# scheme.net
KiCad netlist of a schematic drawn in Altium Designer
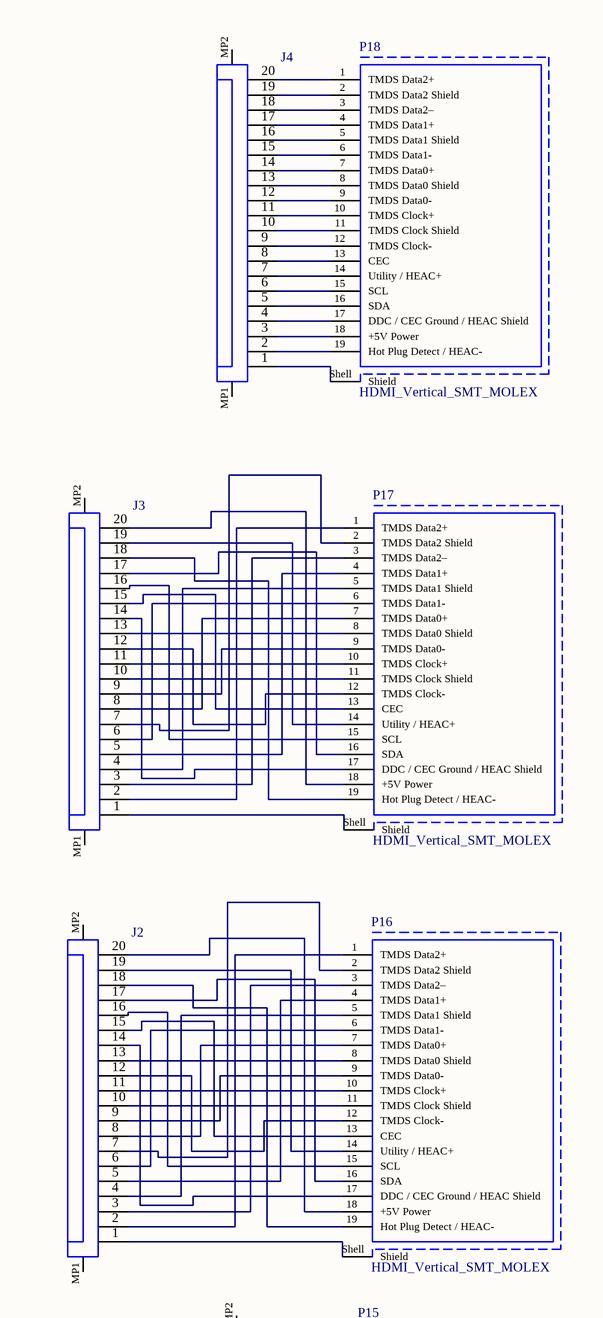
[diagram p0: scheme.SchDoc, top]
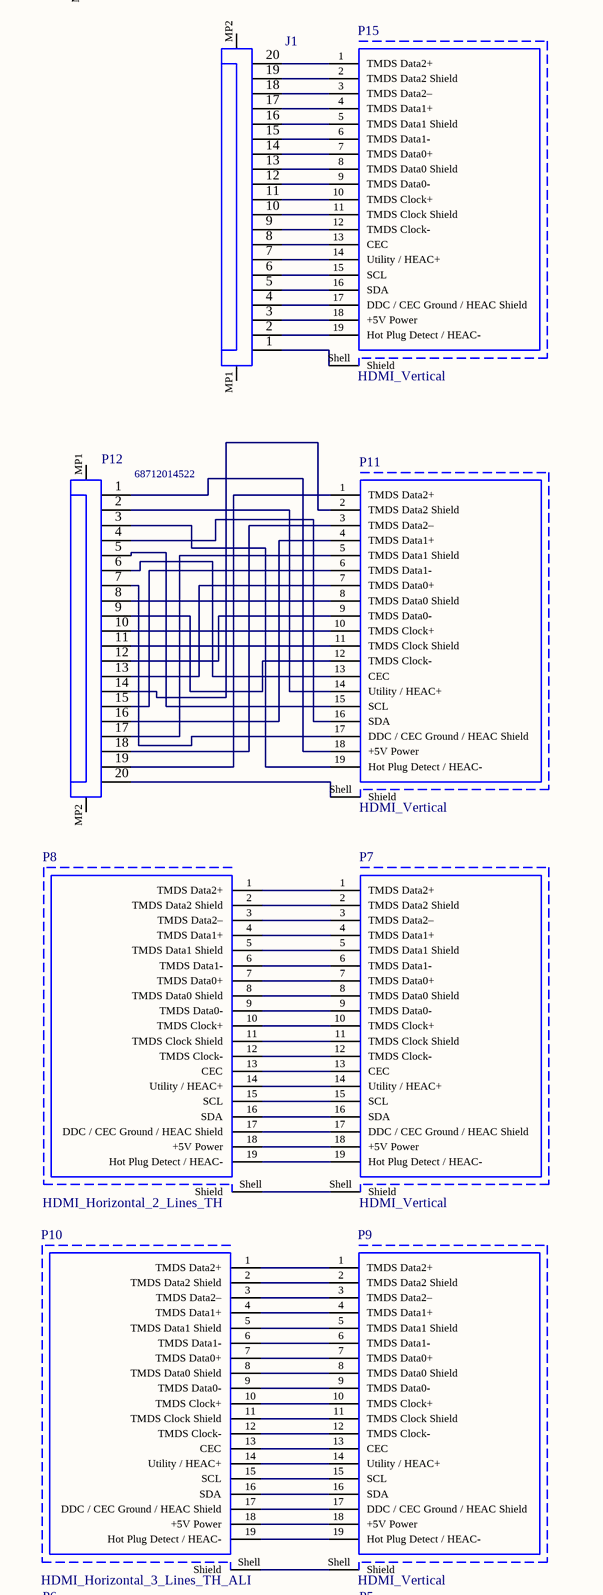
[diagram p1: scheme.SchDoc, centre]
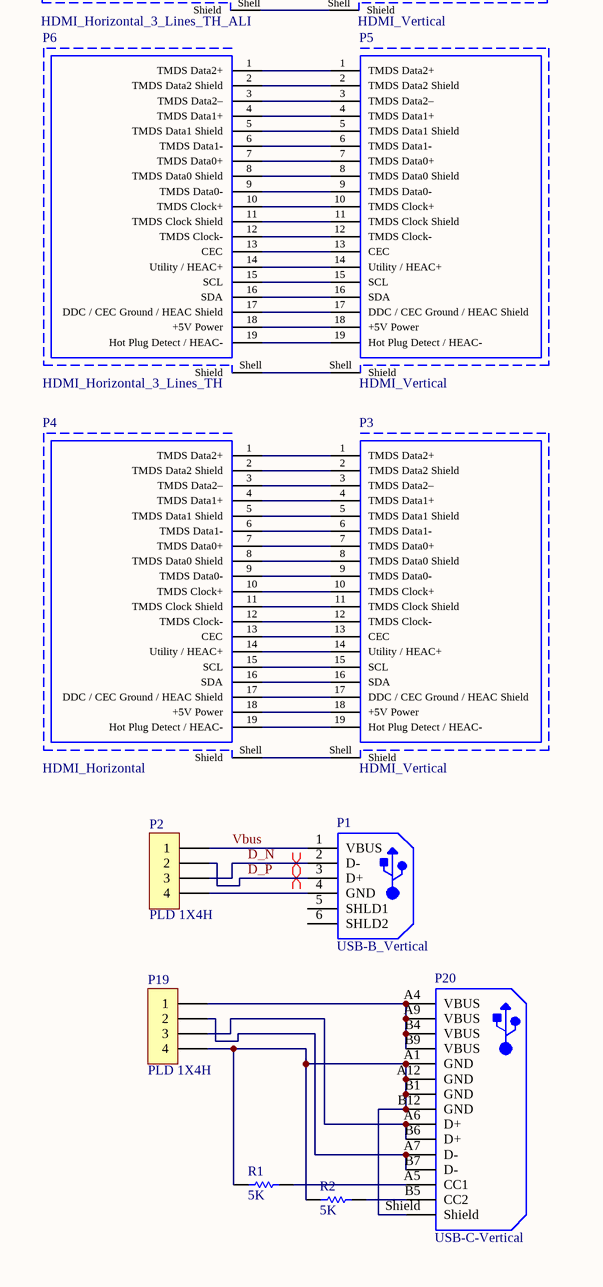
[diagram p2: scheme.SchDoc, bottom]

(export (version "E")
  (design (tool "Eeschema 10.0.6"))
  (components
    (comp (ref "J1")
      (value "68712014522")
      (footprint "FFC_20pin_0.5mm")
      (description "SMT ZIF Connectors WR-FPC, Horizontal, Bottom Contact, pitch 0.5 mm, 20 pins")
      (fields (field (name "MANUFACTURER") "Wurth Elektronik") (field (name "PUBLISHER") "WurthElektronik"))
      (libsource (lib "library") (part "FFC 20 pin"))
    )
    (comp (ref "J2")
      (value "68712014522")
      (footprint "FFC_20pin_0.5mm")
      (description "SMT ZIF Connectors WR-FPC, Horizontal, Bottom Contact, pitch 0.5 mm, 20 pins")
      (fields (field (name "MANUFACTURER") "Wurth Elektronik") (field (name "PUBLISHER") "WurthElektronik"))
      (libsource (lib "library") (part "FFC 20 pin"))
    )
    (comp (ref "J3")
      (value "68712014522")
      (footprint "FFC_20pin_0.5mm")
      (description "SMT ZIF Connectors WR-FPC, Horizontal, Bottom Contact, pitch 0.5 mm, 20 pins")
      (fields (field (name "MANUFACTURER") "Wurth Elektronik") (field (name "PUBLISHER") "WurthElektronik"))
      (libsource (lib "library") (part "FFC 20 pin"))
    )
    (comp (ref "J4")
      (value "68712014522")
      (footprint "FFC_20pin_0.5mm")
      (description "SMT ZIF Connectors WR-FPC, Horizontal, Bottom Contact, pitch 0.5 mm, 20 pins")
      (fields (field (name "MANUFACTURER") "Wurth Elektronik") (field (name "PUBLISHER") "WurthElektronik"))
      (libsource (lib "library") (part "FFC 20 pin"))
    )
    (comp (ref "P1")
      (value "USB-B_Vertical")
      (footprint "USB-B_Vertical")
      (libsource (lib "library") (part "USB-B_Vertical"))
    )
    (comp (ref "P2")
      (value "PLD 1X4H")
      (footprint "PLD 1X4H")
      (description "Header, 4-Pin, SIngle row, Right Angle")
      (libsource (lib "library") (part "PLD 1X4H"))
    )
    (comp (ref "P3")
      (value "HDMI_Vertical")
      (footprint "HDMI Vertical")
      (libsource (lib "library") (part "HDMI_Vertical"))
    )
    (comp (ref "P4")
      (value "HDMI_Horizontal")
      (footprint "HDMI HORIZONTAL")
      (libsource (lib "library") (part "HDMI_Horizontal"))
    )
    (comp (ref "P5")
      (value "HDMI_Vertical")
      (footprint "HDMI Vertical")
      (libsource (lib "library") (part "HDMI_Vertical"))
    )
    (comp (ref "P6")
      (value "HDMI_Horizontal_3_Lines_TH")
      (footprint "HDMI HORIZONTAL 3 LINES TH")
      (libsource (lib "library") (part "HDMI_Horizontal_3_Lines_TH"))
    )
    (comp (ref "P7")
      (value "HDMI_Vertical")
      (footprint "HDMI Vertical")
      (libsource (lib "library") (part "HDMI_Vertical"))
    )
    (comp (ref "P8")
      (value "HDMI_Horizontal_2_Lines_TH")
      (footprint "HDMI HORIZONTAL 2 LINES TH")
      (libsource (lib "library") (part "HDMI_Horizontal_2_Lines_TH"))
    )
    (comp (ref "P9")
      (value "HDMI_Vertical")
      (footprint "HDMI Vertical")
      (libsource (lib "library") (part "HDMI_Vertical"))
    )
    (comp (ref "P10")
      (value "HDMI_Horizontal_3_Lines_TH_ALI")
      (footprint "HDMI HORIZONTAL 3 LINES TH ALI")
      (libsource (lib "library") (part "HDMI_Horizontal_3_Lines_TH_ALI"))
    )
    (comp (ref "P11")
      (value "HDMI_Vertical")
      (footprint "HDMI Vertical")
      (libsource (lib "library") (part "HDMI_Vertical"))
    )
    (comp (ref "P12")
      (value "68712014522")
      (footprint "68712014522")
      (description "SMT ZIF Connectors WR-FPC, Horizontal, Bottom Contact, pitch 0.5 mm, 20 pins")
      (fields (field (name "MANUFACTURER") "Wurth Elektronik") (field (name "PUBLISHER") "WurthElektronik"))
      (libsource (lib "library") (part "CMP-1502-01535-1"))
    )
    (comp (ref "P15")
      (value "HDMI_Vertical")
      (footprint "HDMI Vertical")
      (libsource (lib "library") (part "HDMI_Vertical"))
    )
    (comp (ref "P16")
      (value "HDMI_Vertical_SMT_MOLEX")
      (footprint "HDMI VERTICAL SMT")
      (libsource (lib "library") (part "HDMI_Vertical_SMT_MOLEX"))
    )
    (comp (ref "P17")
      (value "HDMI_Vertical_SMT_MOLEX")
      (footprint "HDMI VERTICAL SMT")
      (libsource (lib "library") (part "HDMI_Vertical_SMT_MOLEX"))
    )
    (comp (ref "P18")
      (value "HDMI_Vertical_SMT_MOLEX")
      (footprint "HDMI VERTICAL SMT")
      (libsource (lib "library") (part "HDMI_Vertical_SMT_MOLEX"))
    )
    (comp (ref "P19")
      (value "PLD 1X4H")
      (footprint "PLD 1X4H")
      (description "Header, 4-Pin, SIngle row, Right Angle")
      (libsource (lib "library") (part "PLD 1X4H"))
    )
    (comp (ref "P20")
      (value "USB-C-Vertical")
      (footprint "USB-C")
      (libsource (lib "library") (part "USB-C-Vertical"))
    )
    (comp (ref "R1")
      (value "5K")
      (footprint "1206")
      (description "Resistor 1206")
      (libsource (lib "library") (part "Resistor"))
    )
    (comp (ref "R2")
      (value "5K")
      (footprint "1206")
      (description "Resistor 1206")
      (libsource (lib "library") (part "Resistor"))
    )
  )
  (nets
    (net (code "1") (name "/D_N") (class "Default")
      (node (ref "P1") (pin "2") (pinfunction "D-_2") (pintype "passive"))
      (node (ref "P2") (pin "3") (pinfunction "3_3") (pintype "passive"))
    )
    (net (code "2") (name "/D_P") (class "Default")
      (node (ref "P1") (pin "3") (pinfunction "D+_3") (pintype "passive"))
      (node (ref "P2") (pin "2") (pinfunction "2_2") (pintype "passive"))
    )
    (net (code "3") (name "/Vbus") (class "Default")
      (node (ref "P1") (pin "1") (pinfunction "VBUS_1") (pintype "passive"))
      (node (ref "P2") (pin "1") (pinfunction "1_1") (pintype "passive"))
    )
    (net (code "4") (name "Net-(P1-GND)") (class "Default")
      (node (ref "P1") (pin "4") (pinfunction "GND_4") (pintype "passive"))
      (node (ref "P2") (pin "4") (pinfunction "4_4") (pintype "passive"))
    )
    (net (code "5") (name "Net-(P3-+5V_Power)") (class "Default")
      (node (ref "P3") (pin "18") (pinfunction "+5V_Power_18") (pintype "passive"))
      (node (ref "P4") (pin "18") (pinfunction "+5V_Power_18") (pintype "passive"))
    )
    (net (code "6") (name "Net-(P3-CEC)") (class "Default")
      (node (ref "P3") (pin "13") (pinfunction "CEC_13") (pintype "passive"))
      (node (ref "P4") (pin "13") (pinfunction "CEC_13") (pintype "passive"))
    )
    (net (code "7") (name "Net-(P3-DDC_{slash}_CEC_Ground_{slash}_HEAC_Shield)") (class "Default")
      (node (ref "P3") (pin "17") (pinfunction "DDC_/_CEC_Ground_/_HEAC_Shield_17") (pintype "passive"))
      (node (ref "P4") (pin "17") (pinfunction "DDC_/_CEC_Ground_/_HEAC_Shield_17") (pintype "passive"))
    )
    (net (code "8") (name "Net-(P3-Hot_Plug_Detect_{slash}_HEAC-)") (class "Default")
      (node (ref "P3") (pin "19") (pinfunction "Hot_Plug_Detect_/_HEAC-_19") (pintype "passive"))
      (node (ref "P4") (pin "19") (pinfunction "Hot_Plug_Detect_/_HEAC-_19") (pintype "passive"))
    )
    (net (code "9") (name "Net-(P3-SCL)") (class "Default")
      (node (ref "P3") (pin "15") (pinfunction "SCL_15") (pintype "passive"))
      (node (ref "P4") (pin "15") (pinfunction "SCL_15") (pintype "passive"))
    )
    (net (code "10") (name "Net-(P3-SDA)") (class "Default")
      (node (ref "P3") (pin "16") (pinfunction "SDA_16") (pintype "passive"))
      (node (ref "P4") (pin "16") (pinfunction "SDA_16") (pintype "passive"))
    )
    (net (code "11") (name "Net-(P3-Shield)") (class "Default")
      (node (ref "P3") (pin "Shell") (pinfunction "Shield_Shell") (pintype "passive"))
      (node (ref "P4") (pin "Shell") (pinfunction "Shield_Shell") (pintype "passive"))
    )
    (net (code "12") (name "Net-(P3-TMDS_Clock+)") (class "Default")
      (node (ref "P3") (pin "10") (pinfunction "TMDS_Clock+_10") (pintype "passive"))
      (node (ref "P4") (pin "10") (pinfunction "TMDS_Clock+_10") (pintype "passive"))
    )
    (net (code "13") (name "Net-(P3-TMDS_Clock-)") (class "Default")
      (node (ref "P3") (pin "12") (pinfunction "TMDS_Clock-_12") (pintype "passive"))
      (node (ref "P4") (pin "12") (pinfunction "TMDS_Clock-_12") (pintype "passive"))
    )
    (net (code "14") (name "Net-(P3-TMDS_Clock_Shield)") (class "Default")
      (node (ref "P3") (pin "11") (pinfunction "TMDS_Clock_Shield_11") (pintype "passive"))
      (node (ref "P4") (pin "11") (pinfunction "TMDS_Clock_Shield_11") (pintype "passive"))
    )
    (net (code "15") (name "Net-(P3-TMDS_Data0+)") (class "Default")
      (node (ref "P3") (pin "7") (pinfunction "TMDS_Data0+_7") (pintype "passive"))
      (node (ref "P4") (pin "7") (pinfunction "TMDS_Data0+_7") (pintype "passive"))
    )
    (net (code "16") (name "Net-(P3-TMDS_Data0-)") (class "Default")
      (node (ref "P3") (pin "9") (pinfunction "TMDS_Data0-_9") (pintype "passive"))
      (node (ref "P4") (pin "9") (pinfunction "TMDS_Data0-_9") (pintype "passive"))
    )
    (net (code "17") (name "Net-(P3-TMDS_Data0_Shield)") (class "Default")
      (node (ref "P3") (pin "8") (pinfunction "TMDS_Data0_Shield_8") (pintype "passive"))
      (node (ref "P4") (pin "8") (pinfunction "TMDS_Data0_Shield_8") (pintype "passive"))
    )
    (net (code "18") (name "Net-(P3-TMDS_Data1+)") (class "Default")
      (node (ref "P3") (pin "4") (pinfunction "TMDS_Data1+_4") (pintype "passive"))
      (node (ref "P4") (pin "4") (pinfunction "TMDS_Data1+_4") (pintype "passive"))
    )
    (net (code "19") (name "Net-(P3-TMDS_Data1-)") (class "Default")
      (node (ref "P3") (pin "6") (pinfunction "TMDS_Data1-_6") (pintype "passive"))
      (node (ref "P4") (pin "6") (pinfunction "TMDS_Data1-_6") (pintype "passive"))
    )
    (net (code "20") (name "Net-(P3-TMDS_Data1_Shield)") (class "Default")
      (node (ref "P3") (pin "5") (pinfunction "TMDS_Data1_Shield_5") (pintype "passive"))
      (node (ref "P4") (pin "5") (pinfunction "TMDS_Data1_Shield_5") (pintype "passive"))
    )
    (net (code "21") (name "Net-(P3-TMDS_Data2+)") (class "Default")
      (node (ref "P3") (pin "1") (pinfunction "TMDS_Data2+_1") (pintype "passive"))
      (node (ref "P4") (pin "1") (pinfunction "TMDS_Data2+_1") (pintype "passive"))
    )
    (net (code "22") (name "Net-(P3-TMDS_Data2_Shield)") (class "Default")
      (node (ref "P3") (pin "2") (pinfunction "TMDS_Data2_Shield_2") (pintype "passive"))
      (node (ref "P4") (pin "2") (pinfunction "TMDS_Data2_Shield_2") (pintype "passive"))
    )
    (net (code "23") (name "Net-(P3-TMDS_Data2–)") (class "Default")
      (node (ref "P3") (pin "3") (pinfunction "TMDS_Data2–_3") (pintype "passive"))
      (node (ref "P4") (pin "3") (pinfunction "TMDS_Data2–_3") (pintype "passive"))
    )
    (net (code "24") (name "Net-(P3-Utility_{slash}_HEAC+)") (class "Default")
      (node (ref "P3") (pin "14") (pinfunction "Utility_/_HEAC+_14") (pintype "passive"))
      (node (ref "P4") (pin "14") (pinfunction "Utility_/_HEAC+_14") (pintype "passive"))
    )
    (net (code "25") (name "Net-(P5-+5V_Power)") (class "Default")
      (node (ref "P5") (pin "18") (pinfunction "+5V_Power_18") (pintype "passive"))
      (node (ref "P6") (pin "18") (pinfunction "+5V_Power_18") (pintype "passive"))
    )
    (net (code "26") (name "Net-(P5-CEC)") (class "Default")
      (node (ref "P5") (pin "13") (pinfunction "CEC_13") (pintype "passive"))
      (node (ref "P6") (pin "13") (pinfunction "CEC_13") (pintype "passive"))
    )
    (net (code "27") (name "Net-(P5-DDC_{slash}_CEC_Ground_{slash}_HEAC_Shield)") (class "Default")
      (node (ref "P5") (pin "17") (pinfunction "DDC_/_CEC_Ground_/_HEAC_Shield_17") (pintype "passive"))
      (node (ref "P6") (pin "17") (pinfunction "DDC_/_CEC_Ground_/_HEAC_Shield_17") (pintype "passive"))
    )
    (net (code "28") (name "Net-(P5-Hot_Plug_Detect_{slash}_HEAC-)") (class "Default")
      (node (ref "P5") (pin "19") (pinfunction "Hot_Plug_Detect_/_HEAC-_19") (pintype "passive"))
      (node (ref "P6") (pin "19") (pinfunction "Hot_Plug_Detect_/_HEAC-_19") (pintype "passive"))
    )
    (net (code "29") (name "Net-(P5-SCL)") (class "Default")
      (node (ref "P5") (pin "15") (pinfunction "SCL_15") (pintype "passive"))
      (node (ref "P6") (pin "15") (pinfunction "SCL_15") (pintype "passive"))
    )
    (net (code "30") (name "Net-(P5-SDA)") (class "Default")
      (node (ref "P5") (pin "16") (pinfunction "SDA_16") (pintype "passive"))
      (node (ref "P6") (pin "16") (pinfunction "SDA_16") (pintype "passive"))
    )
    (net (code "31") (name "Net-(P5-Shield)") (class "Default")
      (node (ref "P5") (pin "Shell") (pinfunction "Shield_Shell") (pintype "passive"))
      (node (ref "P6") (pin "Shell") (pinfunction "Shield_Shell") (pintype "passive"))
    )
    (net (code "32") (name "Net-(P5-TMDS_Clock+)") (class "Default")
      (node (ref "P5") (pin "10") (pinfunction "TMDS_Clock+_10") (pintype "passive"))
      (node (ref "P6") (pin "10") (pinfunction "TMDS_Clock+_10") (pintype "passive"))
    )
    (net (code "33") (name "Net-(P5-TMDS_Clock-)") (class "Default")
      (node (ref "P5") (pin "12") (pinfunction "TMDS_Clock-_12") (pintype "passive"))
      (node (ref "P6") (pin "12") (pinfunction "TMDS_Clock-_12") (pintype "passive"))
    )
    (net (code "34") (name "Net-(P5-TMDS_Clock_Shield)") (class "Default")
      (node (ref "P5") (pin "11") (pinfunction "TMDS_Clock_Shield_11") (pintype "passive"))
      (node (ref "P6") (pin "11") (pinfunction "TMDS_Clock_Shield_11") (pintype "passive"))
    )
    (net (code "35") (name "Net-(P5-TMDS_Data0+)") (class "Default")
      (node (ref "P5") (pin "7") (pinfunction "TMDS_Data0+_7") (pintype "passive"))
      (node (ref "P6") (pin "7") (pinfunction "TMDS_Data0+_7") (pintype "passive"))
    )
    (net (code "36") (name "Net-(P5-TMDS_Data0-)") (class "Default")
      (node (ref "P5") (pin "9") (pinfunction "TMDS_Data0-_9") (pintype "passive"))
      (node (ref "P6") (pin "9") (pinfunction "TMDS_Data0-_9") (pintype "passive"))
    )
    (net (code "37") (name "Net-(P5-TMDS_Data0_Shield)") (class "Default")
      (node (ref "P5") (pin "8") (pinfunction "TMDS_Data0_Shield_8") (pintype "passive"))
      (node (ref "P6") (pin "8") (pinfunction "TMDS_Data0_Shield_8") (pintype "passive"))
    )
    (net (code "38") (name "Net-(P5-TMDS_Data1+)") (class "Default")
      (node (ref "P5") (pin "4") (pinfunction "TMDS_Data1+_4") (pintype "passive"))
      (node (ref "P6") (pin "4") (pinfunction "TMDS_Data1+_4") (pintype "passive"))
    )
    (net (code "39") (name "Net-(P5-TMDS_Data1-)") (class "Default")
      (node (ref "P5") (pin "6") (pinfunction "TMDS_Data1-_6") (pintype "passive"))
      (node (ref "P6") (pin "6") (pinfunction "TMDS_Data1-_6") (pintype "passive"))
    )
    (net (code "40") (name "Net-(P5-TMDS_Data1_Shield)") (class "Default")
      (node (ref "P5") (pin "5") (pinfunction "TMDS_Data1_Shield_5") (pintype "passive"))
      (node (ref "P6") (pin "5") (pinfunction "TMDS_Data1_Shield_5") (pintype "passive"))
    )
    (net (code "41") (name "Net-(P5-TMDS_Data2+)") (class "Default")
      (node (ref "P5") (pin "1") (pinfunction "TMDS_Data2+_1") (pintype "passive"))
      (node (ref "P6") (pin "1") (pinfunction "TMDS_Data2+_1") (pintype "passive"))
    )
    (net (code "42") (name "Net-(P5-TMDS_Data2_Shield)") (class "Default")
      (node (ref "P5") (pin "2") (pinfunction "TMDS_Data2_Shield_2") (pintype "passive"))
      (node (ref "P6") (pin "2") (pinfunction "TMDS_Data2_Shield_2") (pintype "passive"))
    )
    (net (code "43") (name "Net-(P5-TMDS_Data2–)") (class "Default")
      (node (ref "P5") (pin "3") (pinfunction "TMDS_Data2–_3") (pintype "passive"))
      (node (ref "P6") (pin "3") (pinfunction "TMDS_Data2–_3") (pintype "passive"))
    )
    (net (code "44") (name "Net-(P5-Utility_{slash}_HEAC+)") (class "Default")
      (node (ref "P5") (pin "14") (pinfunction "Utility_/_HEAC+_14") (pintype "passive"))
      (node (ref "P6") (pin "14") (pinfunction "Utility_/_HEAC+_14") (pintype "passive"))
    )
    (net (code "45") (name "Net-(P7-+5V_Power)") (class "Default")
      (node (ref "P7") (pin "18") (pinfunction "+5V_Power_18") (pintype "passive"))
      (node (ref "P8") (pin "18") (pinfunction "+5V_Power_18") (pintype "passive"))
    )
    (net (code "46") (name "Net-(P7-CEC)") (class "Default")
      (node (ref "P7") (pin "13") (pinfunction "CEC_13") (pintype "passive"))
      (node (ref "P8") (pin "13") (pinfunction "CEC_13") (pintype "passive"))
    )
    (net (code "47") (name "Net-(P7-DDC_{slash}_CEC_Ground_{slash}_HEAC_Shield)") (class "Default")
      (node (ref "P7") (pin "17") (pinfunction "DDC_/_CEC_Ground_/_HEAC_Shield_17") (pintype "passive"))
      (node (ref "P8") (pin "17") (pinfunction "DDC_/_CEC_Ground_/_HEAC_Shield_17") (pintype "passive"))
    )
    (net (code "48") (name "Net-(P7-Hot_Plug_Detect_{slash}_HEAC-)") (class "Default")
      (node (ref "P7") (pin "19") (pinfunction "Hot_Plug_Detect_/_HEAC-_19") (pintype "passive"))
      (node (ref "P8") (pin "19") (pinfunction "Hot_Plug_Detect_/_HEAC-_19") (pintype "passive"))
    )
    (net (code "49") (name "Net-(P7-SCL)") (class "Default")
      (node (ref "P7") (pin "15") (pinfunction "SCL_15") (pintype "passive"))
      (node (ref "P8") (pin "15") (pinfunction "SCL_15") (pintype "passive"))
    )
    (net (code "50") (name "Net-(P7-SDA)") (class "Default")
      (node (ref "P7") (pin "16") (pinfunction "SDA_16") (pintype "passive"))
      (node (ref "P8") (pin "16") (pinfunction "SDA_16") (pintype "passive"))
    )
    (net (code "51") (name "Net-(P7-Shield)") (class "Default")
      (node (ref "P7") (pin "Shell") (pinfunction "Shield_Shell") (pintype "passive"))
      (node (ref "P8") (pin "Shell") (pinfunction "Shield_Shell") (pintype "passive"))
    )
    (net (code "52") (name "Net-(P7-TMDS_Clock+)") (class "Default")
      (node (ref "P7") (pin "10") (pinfunction "TMDS_Clock+_10") (pintype "passive"))
      (node (ref "P8") (pin "10") (pinfunction "TMDS_Clock+_10") (pintype "passive"))
    )
    (net (code "53") (name "Net-(P7-TMDS_Clock-)") (class "Default")
      (node (ref "P7") (pin "12") (pinfunction "TMDS_Clock-_12") (pintype "passive"))
      (node (ref "P8") (pin "12") (pinfunction "TMDS_Clock-_12") (pintype "passive"))
    )
    (net (code "54") (name "Net-(P7-TMDS_Clock_Shield)") (class "Default")
      (node (ref "P7") (pin "11") (pinfunction "TMDS_Clock_Shield_11") (pintype "passive"))
      (node (ref "P8") (pin "11") (pinfunction "TMDS_Clock_Shield_11") (pintype "passive"))
    )
    (net (code "55") (name "Net-(P7-TMDS_Data0+)") (class "Default")
      (node (ref "P7") (pin "7") (pinfunction "TMDS_Data0+_7") (pintype "passive"))
      (node (ref "P8") (pin "7") (pinfunction "TMDS_Data0+_7") (pintype "passive"))
    )
    (net (code "56") (name "Net-(P7-TMDS_Data0-)") (class "Default")
      (node (ref "P7") (pin "9") (pinfunction "TMDS_Data0-_9") (pintype "passive"))
      (node (ref "P8") (pin "9") (pinfunction "TMDS_Data0-_9") (pintype "passive"))
    )
    (net (code "57") (name "Net-(P7-TMDS_Data0_Shield)") (class "Default")
      (node (ref "P7") (pin "8") (pinfunction "TMDS_Data0_Shield_8") (pintype "passive"))
      (node (ref "P8") (pin "8") (pinfunction "TMDS_Data0_Shield_8") (pintype "passive"))
    )
    (net (code "58") (name "Net-(P7-TMDS_Data1+)") (class "Default")
      (node (ref "P7") (pin "4") (pinfunction "TMDS_Data1+_4") (pintype "passive"))
      (node (ref "P8") (pin "4") (pinfunction "TMDS_Data1+_4") (pintype "passive"))
    )
    (net (code "59") (name "Net-(P7-TMDS_Data1-)") (class "Default")
      (node (ref "P7") (pin "6") (pinfunction "TMDS_Data1-_6") (pintype "passive"))
      (node (ref "P8") (pin "6") (pinfunction "TMDS_Data1-_6") (pintype "passive"))
    )
    (net (code "60") (name "Net-(P7-TMDS_Data1_Shield)") (class "Default")
      (node (ref "P7") (pin "5") (pinfunction "TMDS_Data1_Shield_5") (pintype "passive"))
      (node (ref "P8") (pin "5") (pinfunction "TMDS_Data1_Shield_5") (pintype "passive"))
    )
    (net (code "61") (name "Net-(P7-TMDS_Data2+)") (class "Default")
      (node (ref "P7") (pin "1") (pinfunction "TMDS_Data2+_1") (pintype "passive"))
      (node (ref "P8") (pin "1") (pinfunction "TMDS_Data2+_1") (pintype "passive"))
    )
    (net (code "62") (name "Net-(P7-TMDS_Data2_Shield)") (class "Default")
      (node (ref "P7") (pin "2") (pinfunction "TMDS_Data2_Shield_2") (pintype "passive"))
      (node (ref "P8") (pin "2") (pinfunction "TMDS_Data2_Shield_2") (pintype "passive"))
    )
    (net (code "63") (name "Net-(P7-TMDS_Data2–)") (class "Default")
      (node (ref "P7") (pin "3") (pinfunction "TMDS_Data2–_3") (pintype "passive"))
      (node (ref "P8") (pin "3") (pinfunction "TMDS_Data2–_3") (pintype "passive"))
    )
    (net (code "64") (name "Net-(P7-Utility_{slash}_HEAC+)") (class "Default")
      (node (ref "P7") (pin "14") (pinfunction "Utility_/_HEAC+_14") (pintype "passive"))
      (node (ref "P8") (pin "14") (pinfunction "Utility_/_HEAC+_14") (pintype "passive"))
    )
    (net (code "65") (name "Net-(P10-+5V_Power)") (class "Default")
      (node (ref "P10") (pin "18") (pinfunction "+5V_Power_18") (pintype "passive"))
      (node (ref "P9") (pin "18") (pinfunction "+5V_Power_18") (pintype "passive"))
    )
    (net (code "66") (name "Net-(P10-CEC)") (class "Default")
      (node (ref "P10") (pin "13") (pinfunction "CEC_13") (pintype "passive"))
      (node (ref "P9") (pin "13") (pinfunction "CEC_13") (pintype "passive"))
    )
    (net (code "67") (name "Net-(P10-DDC_{slash}_CEC_Ground_{slash}_HEAC_Shield)") (class "Default")
      (node (ref "P10") (pin "17") (pinfunction "DDC_/_CEC_Ground_/_HEAC_Shield_17") (pintype "passive"))
      (node (ref "P9") (pin "17") (pinfunction "DDC_/_CEC_Ground_/_HEAC_Shield_17") (pintype "passive"))
    )
    (net (code "68") (name "Net-(P10-Hot_Plug_Detect_{slash}_HEAC-)") (class "Default")
      (node (ref "P10") (pin "19") (pinfunction "Hot_Plug_Detect_/_HEAC-_19") (pintype "passive"))
      (node (ref "P9") (pin "19") (pinfunction "Hot_Plug_Detect_/_HEAC-_19") (pintype "passive"))
    )
    (net (code "69") (name "Net-(P10-SCL)") (class "Default")
      (node (ref "P10") (pin "15") (pinfunction "SCL_15") (pintype "passive"))
      (node (ref "P9") (pin "15") (pinfunction "SCL_15") (pintype "passive"))
    )
    (net (code "70") (name "Net-(P10-SDA)") (class "Default")
      (node (ref "P10") (pin "16") (pinfunction "SDA_16") (pintype "passive"))
      (node (ref "P9") (pin "16") (pinfunction "SDA_16") (pintype "passive"))
    )
    (net (code "71") (name "Net-(P10-Shield)") (class "Default")
      (node (ref "P10") (pin "Shell") (pinfunction "Shield_Shell") (pintype "passive"))
      (node (ref "P9") (pin "Shell") (pinfunction "Shield_Shell") (pintype "passive"))
    )
    (net (code "72") (name "Net-(P10-TMDS_Clock+)") (class "Default")
      (node (ref "P10") (pin "10") (pinfunction "TMDS_Clock+_10") (pintype "passive"))
      (node (ref "P9") (pin "10") (pinfunction "TMDS_Clock+_10") (pintype "passive"))
    )
    (net (code "73") (name "Net-(P10-TMDS_Clock-)") (class "Default")
      (node (ref "P10") (pin "12") (pinfunction "TMDS_Clock-_12") (pintype "passive"))
      (node (ref "P9") (pin "12") (pinfunction "TMDS_Clock-_12") (pintype "passive"))
    )
    (net (code "74") (name "Net-(P10-TMDS_Clock_Shield)") (class "Default")
      (node (ref "P10") (pin "11") (pinfunction "TMDS_Clock_Shield_11") (pintype "passive"))
      (node (ref "P9") (pin "11") (pinfunction "TMDS_Clock_Shield_11") (pintype "passive"))
    )
    (net (code "75") (name "Net-(P10-TMDS_Data0+)") (class "Default")
      (node (ref "P10") (pin "7") (pinfunction "TMDS_Data0+_7") (pintype "passive"))
      (node (ref "P9") (pin "7") (pinfunction "TMDS_Data0+_7") (pintype "passive"))
    )
    (net (code "76") (name "Net-(P10-TMDS_Data0-)") (class "Default")
      (node (ref "P10") (pin "9") (pinfunction "TMDS_Data0-_9") (pintype "passive"))
      (node (ref "P9") (pin "9") (pinfunction "TMDS_Data0-_9") (pintype "passive"))
    )
    (net (code "77") (name "Net-(P10-TMDS_Data0_Shield)") (class "Default")
      (node (ref "P10") (pin "8") (pinfunction "TMDS_Data0_Shield_8") (pintype "passive"))
      (node (ref "P9") (pin "8") (pinfunction "TMDS_Data0_Shield_8") (pintype "passive"))
    )
    (net (code "78") (name "Net-(P10-TMDS_Data1+)") (class "Default")
      (node (ref "P10") (pin "4") (pinfunction "TMDS_Data1+_4") (pintype "passive"))
      (node (ref "P9") (pin "4") (pinfunction "TMDS_Data1+_4") (pintype "passive"))
    )
    (net (code "79") (name "Net-(P10-TMDS_Data1-)") (class "Default")
      (node (ref "P10") (pin "6") (pinfunction "TMDS_Data1-_6") (pintype "passive"))
      (node (ref "P9") (pin "6") (pinfunction "TMDS_Data1-_6") (pintype "passive"))
    )
    (net (code "80") (name "Net-(P10-TMDS_Data1_Shield)") (class "Default")
      (node (ref "P10") (pin "5") (pinfunction "TMDS_Data1_Shield_5") (pintype "passive"))
      (node (ref "P9") (pin "5") (pinfunction "TMDS_Data1_Shield_5") (pintype "passive"))
    )
    (net (code "81") (name "Net-(P10-TMDS_Data2+)") (class "Default")
      (node (ref "P10") (pin "1") (pinfunction "TMDS_Data2+_1") (pintype "passive"))
      (node (ref "P9") (pin "1") (pinfunction "TMDS_Data2+_1") (pintype "passive"))
    )
    (net (code "82") (name "Net-(P10-TMDS_Data2_Shield)") (class "Default")
      (node (ref "P10") (pin "2") (pinfunction "TMDS_Data2_Shield_2") (pintype "passive"))
      (node (ref "P9") (pin "2") (pinfunction "TMDS_Data2_Shield_2") (pintype "passive"))
    )
    (net (code "83") (name "Net-(P10-TMDS_Data2–)") (class "Default")
      (node (ref "P10") (pin "3") (pinfunction "TMDS_Data2–_3") (pintype "passive"))
      (node (ref "P9") (pin "3") (pinfunction "TMDS_Data2–_3") (pintype "passive"))
    )
    (net (code "84") (name "Net-(P10-Utility_{slash}_HEAC+)") (class "Default")
      (node (ref "P10") (pin "14") (pinfunction "Utility_/_HEAC+_14") (pintype "passive"))
      (node (ref "P9") (pin "14") (pinfunction "Utility_/_HEAC+_14") (pintype "passive"))
    )
    (net (code "85") (name "Net-(P11-+5V_Power)") (class "Default")
      (node (ref "P11") (pin "18") (pinfunction "+5V_Power_18") (pintype "passive"))
      (node (ref "P12") (pin "1") (pinfunction "1_1") (pintype "passive"))
    )
    (net (code "86") (name "Net-(P11-CEC)") (class "Default")
      (node (ref "P11") (pin "13") (pinfunction "CEC_13") (pintype "passive"))
      (node (ref "P12") (pin "6") (pinfunction "6_6") (pintype "passive"))
    )
    (net (code "87") (name "Net-(P11-DDC_{slash}_CEC_Ground_{slash}_HEAC_Shield)") (class "Default")
      (node (ref "P11") (pin "17") (pinfunction "DDC_/_CEC_Ground_/_HEAC_Shield_17") (pintype "passive"))
      (node (ref "P12") (pin "7") (pinfunction "7_7") (pintype "passive"))
    )
    (net (code "88") (name "Net-(P11-Hot_Plug_Detect_{slash}_HEAC-)") (class "Default")
      (node (ref "P11") (pin "19") (pinfunction "Hot_Plug_Detect_/_HEAC-_19") (pintype "passive"))
      (node (ref "P12") (pin "3") (pinfunction "3_3") (pintype "passive"))
    )
    (net (code "89") (name "Net-(P11-SCL)") (class "Default")
      (node (ref "P11") (pin "15") (pinfunction "SCL_15") (pintype "passive"))
      (node (ref "P12") (pin "5") (pinfunction "5_5") (pintype "passive"))
    )
    (net (code "90") (name "Net-(P11-SDA)") (class "Default")
      (node (ref "P11") (pin "16") (pinfunction "SDA_16") (pintype "passive"))
      (node (ref "P12") (pin "4") (pinfunction "4_4") (pintype "passive"))
    )
    (net (code "91") (name "Net-(P11-Shield)") (class "Default")
      (node (ref "P11") (pin "Shell") (pinfunction "Shield_Shell") (pintype "passive"))
      (node (ref "P12") (pin "20") (pinfunction "20_20") (pintype "passive"))
    )
    (net (code "92") (name "Net-(P11-TMDS_Clock+)") (class "Default")
      (node (ref "P11") (pin "10") (pinfunction "TMDS_Clock+_10") (pintype "passive"))
      (node (ref "P12") (pin "10") (pinfunction "10_10") (pintype "passive"))
    )
    (net (code "93") (name "Net-(P11-TMDS_Clock-)") (class "Default")
      (node (ref "P11") (pin "12") (pinfunction "TMDS_Clock-_12") (pintype "passive"))
      (node (ref "P12") (pin "9") (pinfunction "9_9") (pintype "passive"))
    )
    (net (code "94") (name "Net-(P11-TMDS_Clock_Shield)") (class "Default")
      (node (ref "P11") (pin "11") (pinfunction "TMDS_Clock_Shield_11") (pintype "passive"))
      (node (ref "P12") (pin "11") (pinfunction "11_11") (pintype "passive"))
    )
    (net (code "95") (name "Net-(P11-TMDS_Data0+)") (class "Default")
      (node (ref "P11") (pin "7") (pinfunction "TMDS_Data0+_7") (pintype "passive"))
      (node (ref "P12") (pin "13") (pinfunction "13_13") (pintype "passive"))
    )
    (net (code "96") (name "Net-(P11-TMDS_Data0-)") (class "Default")
      (node (ref "P11") (pin "9") (pinfunction "TMDS_Data0-_9") (pintype "passive"))
      (node (ref "P12") (pin "12") (pinfunction "12_12") (pintype "passive"))
    )
    (net (code "97") (name "Net-(P11-TMDS_Data0_Shield)") (class "Default")
      (node (ref "P11") (pin "8") (pinfunction "TMDS_Data0_Shield_8") (pintype "passive"))
      (node (ref "P12") (pin "8") (pinfunction "8_8") (pintype "passive"))
    )
    (net (code "98") (name "Net-(P11-TMDS_Data1+)") (class "Default")
      (node (ref "P11") (pin "4") (pinfunction "TMDS_Data1+_4") (pintype "passive"))
      (node (ref "P12") (pin "16") (pinfunction "16_16") (pintype "passive"))
    )
    (net (code "99") (name "Net-(P11-TMDS_Data1-)") (class "Default")
      (node (ref "P11") (pin "6") (pinfunction "TMDS_Data1-_6") (pintype "passive"))
      (node (ref "P12") (pin "15") (pinfunction "15_15") (pintype "passive"))
    )
    (net (code "100") (name "Net-(P11-TMDS_Data1_Shield)") (class "Default")
      (node (ref "P11") (pin "5") (pinfunction "TMDS_Data1_Shield_5") (pintype "passive"))
      (node (ref "P12") (pin "17") (pinfunction "17_17") (pintype "passive"))
    )
    (net (code "101") (name "Net-(P11-TMDS_Data2+)") (class "Default")
      (node (ref "P11") (pin "1") (pinfunction "TMDS_Data2+_1") (pintype "passive"))
      (node (ref "P12") (pin "19") (pinfunction "19_19") (pintype "passive"))
    )
    (net (code "102") (name "Net-(P11-TMDS_Data2_Shield)") (class "Default")
      (node (ref "P11") (pin "2") (pinfunction "TMDS_Data2_Shield_2") (pintype "passive"))
      (node (ref "P12") (pin "14") (pinfunction "14_14") (pintype "passive"))
    )
    (net (code "103") (name "Net-(P11-TMDS_Data2–)") (class "Default")
      (node (ref "P11") (pin "3") (pinfunction "TMDS_Data2–_3") (pintype "passive"))
      (node (ref "P12") (pin "18") (pinfunction "18_18") (pintype "passive"))
    )
    (net (code "104") (name "Net-(P11-Utility_{slash}_HEAC+)") (class "Default")
      (node (ref "P11") (pin "14") (pinfunction "Utility_/_HEAC+_14") (pintype "passive"))
      (node (ref "P12") (pin "2") (pinfunction "2_2") (pintype "passive"))
    )
    (net (code "105") (name "Net-(P15-+5V_Power)") (class "Default")
      (node (ref "J1") (pin "3") (pinfunction "3_3") (pintype "passive"))
      (node (ref "P15") (pin "18") (pinfunction "+5V_Power_18") (pintype "passive"))
    )
    (net (code "106") (name "Net-(P15-CEC)") (class "Default")
      (node (ref "J1") (pin "8") (pinfunction "8_8") (pintype "passive"))
      (node (ref "P15") (pin "13") (pinfunction "CEC_13") (pintype "passive"))
    )
    (net (code "107") (name "Net-(P15-DDC_{slash}_CEC_Ground_{slash}_HEAC_Shield)") (class "Default")
      (node (ref "J1") (pin "4") (pinfunction "4_4") (pintype "passive"))
      (node (ref "P15") (pin "17") (pinfunction "DDC_/_CEC_Ground_/_HEAC_Shield_17") (pintype "passive"))
    )
    (net (code "108") (name "Net-(P15-Hot_Plug_Detect_{slash}_HEAC-)") (class "Default")
      (node (ref "J1") (pin "2") (pinfunction "2_2") (pintype "passive"))
      (node (ref "P15") (pin "19") (pinfunction "Hot_Plug_Detect_/_HEAC-_19") (pintype "passive"))
    )
    (net (code "109") (name "Net-(P15-SCL)") (class "Default")
      (node (ref "J1") (pin "6") (pinfunction "6_6") (pintype "passive"))
      (node (ref "P15") (pin "15") (pinfunction "SCL_15") (pintype "passive"))
    )
    (net (code "110") (name "Net-(P15-SDA)") (class "Default")
      (node (ref "J1") (pin "5") (pinfunction "5_5") (pintype "passive"))
      (node (ref "P15") (pin "16") (pinfunction "SDA_16") (pintype "passive"))
    )
    (net (code "111") (name "Net-(P15-Shield)") (class "Default")
      (node (ref "J1") (pin "1") (pinfunction "1_1") (pintype "passive"))
      (node (ref "P15") (pin "Shell") (pinfunction "Shield_Shell") (pintype "passive"))
    )
    (net (code "112") (name "Net-(P15-TMDS_Clock+)") (class "Default")
      (node (ref "J1") (pin "11") (pinfunction "11_11") (pintype "passive"))
      (node (ref "P15") (pin "10") (pinfunction "TMDS_Clock+_10") (pintype "passive"))
    )
    (net (code "113") (name "Net-(P15-TMDS_Clock-)") (class "Default")
      (node (ref "J1") (pin "9") (pinfunction "9_9") (pintype "passive"))
      (node (ref "P15") (pin "12") (pinfunction "TMDS_Clock-_12") (pintype "passive"))
    )
    (net (code "114") (name "Net-(P15-TMDS_Clock_Shield)") (class "Default")
      (node (ref "J1") (pin "10") (pinfunction "10_10") (pintype "passive"))
      (node (ref "P15") (pin "11") (pinfunction "TMDS_Clock_Shield_11") (pintype "passive"))
    )
    (net (code "115") (name "Net-(P15-TMDS_Data0+)") (class "Default")
      (node (ref "J1") (pin "14") (pinfunction "14_14") (pintype "passive"))
      (node (ref "P15") (pin "7") (pinfunction "TMDS_Data0+_7") (pintype "passive"))
    )
    (net (code "116") (name "Net-(P15-TMDS_Data0-)") (class "Default")
      (node (ref "J1") (pin "12") (pinfunction "12_12") (pintype "passive"))
      (node (ref "P15") (pin "9") (pinfunction "TMDS_Data0-_9") (pintype "passive"))
    )
    (net (code "117") (name "Net-(P15-TMDS_Data0_Shield)") (class "Default")
      (node (ref "J1") (pin "13") (pinfunction "13_13") (pintype "passive"))
      (node (ref "P15") (pin "8") (pinfunction "TMDS_Data0_Shield_8") (pintype "passive"))
    )
    (net (code "118") (name "Net-(P15-TMDS_Data1+)") (class "Default")
      (node (ref "J1") (pin "17") (pinfunction "17_17") (pintype "passive"))
      (node (ref "P15") (pin "4") (pinfunction "TMDS_Data1+_4") (pintype "passive"))
    )
    (net (code "119") (name "Net-(P15-TMDS_Data1-)") (class "Default")
      (node (ref "J1") (pin "15") (pinfunction "15_15") (pintype "passive"))
      (node (ref "P15") (pin "6") (pinfunction "TMDS_Data1-_6") (pintype "passive"))
    )
    (net (code "120") (name "Net-(P15-TMDS_Data1_Shield)") (class "Default")
      (node (ref "J1") (pin "16") (pinfunction "16_16") (pintype "passive"))
      (node (ref "P15") (pin "5") (pinfunction "TMDS_Data1_Shield_5") (pintype "passive"))
    )
    (net (code "121") (name "Net-(P15-TMDS_Data2+)") (class "Default")
      (node (ref "J1") (pin "20") (pinfunction "20_20") (pintype "passive"))
      (node (ref "P15") (pin "1") (pinfunction "TMDS_Data2+_1") (pintype "passive"))
    )
    (net (code "122") (name "Net-(P15-TMDS_Data2_Shield)") (class "Default")
      (node (ref "J1") (pin "19") (pinfunction "19_19") (pintype "passive"))
      (node (ref "P15") (pin "2") (pinfunction "TMDS_Data2_Shield_2") (pintype "passive"))
    )
    (net (code "123") (name "Net-(P15-TMDS_Data2–)") (class "Default")
      (node (ref "J1") (pin "18") (pinfunction "18_18") (pintype "passive"))
      (node (ref "P15") (pin "3") (pinfunction "TMDS_Data2–_3") (pintype "passive"))
    )
    (net (code "124") (name "Net-(P15-Utility_{slash}_HEAC+)") (class "Default")
      (node (ref "J1") (pin "7") (pinfunction "7_7") (pintype "passive"))
      (node (ref "P15") (pin "14") (pinfunction "Utility_/_HEAC+_14") (pintype "passive"))
    )
    (net (code "125") (name "Net-(P16-+5V_Power)") (class "Default")
      (node (ref "J2") (pin "20") (pinfunction "20_20") (pintype "passive"))
      (node (ref "P16") (pin "18") (pinfunction "+5V_Power_18") (pintype "passive"))
    )
    (net (code "126") (name "Net-(P16-CEC)") (class "Default")
      (node (ref "J2") (pin "15") (pinfunction "15_15") (pintype "passive"))
      (node (ref "P16") (pin "13") (pinfunction "CEC_13") (pintype "passive"))
    )
    (net (code "127") (name "Net-(P16-DDC_{slash}_CEC_Ground_{slash}_HEAC_Shield)") (class "Default")
      (node (ref "J2") (pin "14") (pinfunction "14_14") (pintype "passive"))
      (node (ref "P16") (pin "17") (pinfunction "DDC_/_CEC_Ground_/_HEAC_Shield_17") (pintype "passive"))
    )
    (net (code "128") (name "Net-(P16-Hot_Plug_Detect_{slash}_HEAC-)") (class "Default")
      (node (ref "J2") (pin "18") (pinfunction "18_18") (pintype "passive"))
      (node (ref "P16") (pin "19") (pinfunction "Hot_Plug_Detect_/_HEAC-_19") (pintype "passive"))
    )
    (net (code "129") (name "Net-(P16-SCL)") (class "Default")
      (node (ref "J2") (pin "16") (pinfunction "16_16") (pintype "passive"))
      (node (ref "P16") (pin "15") (pinfunction "SCL_15") (pintype "passive"))
    )
    (net (code "130") (name "Net-(P16-SDA)") (class "Default")
      (node (ref "J2") (pin "17") (pinfunction "17_17") (pintype "passive"))
      (node (ref "P16") (pin "16") (pinfunction "SDA_16") (pintype "passive"))
    )
    (net (code "131") (name "Net-(P16-Shield)") (class "Default")
      (node (ref "J2") (pin "1") (pinfunction "1_1") (pintype "passive"))
      (node (ref "P16") (pin "Shell") (pinfunction "Shield_Shell") (pintype "passive"))
    )
    (net (code "132") (name "Net-(P16-TMDS_Clock+)") (class "Default")
      (node (ref "J2") (pin "11") (pinfunction "11_11") (pintype "passive"))
      (node (ref "P16") (pin "10") (pinfunction "TMDS_Clock+_10") (pintype "passive"))
    )
    (net (code "133") (name "Net-(P16-TMDS_Clock-)") (class "Default")
      (node (ref "J2") (pin "12") (pinfunction "12_12") (pintype "passive"))
      (node (ref "P16") (pin "12") (pinfunction "TMDS_Clock-_12") (pintype "passive"))
    )
    (net (code "134") (name "Net-(P16-TMDS_Clock_Shield)") (class "Default")
      (node (ref "J2") (pin "10") (pinfunction "10_10") (pintype "passive"))
      (node (ref "P16") (pin "11") (pinfunction "TMDS_Clock_Shield_11") (pintype "passive"))
    )
    (net (code "135") (name "Net-(P16-TMDS_Data0+)") (class "Default")
      (node (ref "J2") (pin "8") (pinfunction "8_8") (pintype "passive"))
      (node (ref "P16") (pin "7") (pinfunction "TMDS_Data0+_7") (pintype "passive"))
    )
    (net (code "136") (name "Net-(P16-TMDS_Data0-)") (class "Default")
      (node (ref "J2") (pin "9") (pinfunction "9_9") (pintype "passive"))
      (node (ref "P16") (pin "9") (pinfunction "TMDS_Data0-_9") (pintype "passive"))
    )
    (net (code "137") (name "Net-(P16-TMDS_Data0_Shield)") (class "Default")
      (node (ref "J2") (pin "13") (pinfunction "13_13") (pintype "passive"))
      (node (ref "P16") (pin "8") (pinfunction "TMDS_Data0_Shield_8") (pintype "passive"))
    )
    (net (code "138") (name "Net-(P16-TMDS_Data1+)") (class "Default")
      (node (ref "J2") (pin "5") (pinfunction "5_5") (pintype "passive"))
      (node (ref "P16") (pin "4") (pinfunction "TMDS_Data1+_4") (pintype "passive"))
    )
    (net (code "139") (name "Net-(P16-TMDS_Data1-)") (class "Default")
      (node (ref "J2") (pin "6") (pinfunction "6_6") (pintype "passive"))
      (node (ref "P16") (pin "6") (pinfunction "TMDS_Data1-_6") (pintype "passive"))
    )
    (net (code "140") (name "Net-(P16-TMDS_Data1_Shield)") (class "Default")
      (node (ref "J2") (pin "4") (pinfunction "4_4") (pintype "passive"))
      (node (ref "P16") (pin "5") (pinfunction "TMDS_Data1_Shield_5") (pintype "passive"))
    )
    (net (code "141") (name "Net-(P16-TMDS_Data2+)") (class "Default")
      (node (ref "J2") (pin "2") (pinfunction "2_2") (pintype "passive"))
      (node (ref "P16") (pin "1") (pinfunction "TMDS_Data2+_1") (pintype "passive"))
    )
    (net (code "142") (name "Net-(P16-TMDS_Data2_Shield)") (class "Default")
      (node (ref "J2") (pin "7") (pinfunction "7_7") (pintype "passive"))
      (node (ref "P16") (pin "2") (pinfunction "TMDS_Data2_Shield_2") (pintype "passive"))
    )
    (net (code "143") (name "Net-(P16-TMDS_Data2–)") (class "Default")
      (node (ref "J2") (pin "3") (pinfunction "3_3") (pintype "passive"))
      (node (ref "P16") (pin "3") (pinfunction "TMDS_Data2–_3") (pintype "passive"))
    )
    (net (code "144") (name "Net-(P16-Utility_{slash}_HEAC+)") (class "Default")
      (node (ref "J2") (pin "19") (pinfunction "19_19") (pintype "passive"))
      (node (ref "P16") (pin "14") (pinfunction "Utility_/_HEAC+_14") (pintype "passive"))
    )
    (net (code "145") (name "Net-(P17-+5V_Power)") (class "Default")
      (node (ref "J3") (pin "20") (pinfunction "20_20") (pintype "passive"))
      (node (ref "P17") (pin "18") (pinfunction "+5V_Power_18") (pintype "passive"))
    )
    (net (code "146") (name "Net-(P17-CEC)") (class "Default")
      (node (ref "J3") (pin "15") (pinfunction "15_15") (pintype "passive"))
      (node (ref "P17") (pin "13") (pinfunction "CEC_13") (pintype "passive"))
    )
    (net (code "147") (name "Net-(P17-DDC_{slash}_CEC_Ground_{slash}_HEAC_Shield)") (class "Default")
      (node (ref "J3") (pin "14") (pinfunction "14_14") (pintype "passive"))
      (node (ref "P17") (pin "17") (pinfunction "DDC_/_CEC_Ground_/_HEAC_Shield_17") (pintype "passive"))
    )
    (net (code "148") (name "Net-(P17-Hot_Plug_Detect_{slash}_HEAC-)") (class "Default")
      (node (ref "J3") (pin "18") (pinfunction "18_18") (pintype "passive"))
      (node (ref "P17") (pin "19") (pinfunction "Hot_Plug_Detect_/_HEAC-_19") (pintype "passive"))
    )
    (net (code "149") (name "Net-(P17-SCL)") (class "Default")
      (node (ref "J3") (pin "16") (pinfunction "16_16") (pintype "passive"))
      (node (ref "P17") (pin "15") (pinfunction "SCL_15") (pintype "passive"))
    )
    (net (code "150") (name "Net-(P17-SDA)") (class "Default")
      (node (ref "J3") (pin "17") (pinfunction "17_17") (pintype "passive"))
      (node (ref "P17") (pin "16") (pinfunction "SDA_16") (pintype "passive"))
    )
    (net (code "151") (name "Net-(P17-Shield)") (class "Default")
      (node (ref "J3") (pin "1") (pinfunction "1_1") (pintype "passive"))
      (node (ref "P17") (pin "Shell") (pinfunction "Shield_Shell") (pintype "passive"))
    )
    (net (code "152") (name "Net-(P17-TMDS_Clock+)") (class "Default")
      (node (ref "J3") (pin "11") (pinfunction "11_11") (pintype "passive"))
      (node (ref "P17") (pin "10") (pinfunction "TMDS_Clock+_10") (pintype "passive"))
    )
    (net (code "153") (name "Net-(P17-TMDS_Clock-)") (class "Default")
      (node (ref "J3") (pin "12") (pinfunction "12_12") (pintype "passive"))
      (node (ref "P17") (pin "12") (pinfunction "TMDS_Clock-_12") (pintype "passive"))
    )
    (net (code "154") (name "Net-(P17-TMDS_Clock_Shield)") (class "Default")
      (node (ref "J3") (pin "10") (pinfunction "10_10") (pintype "passive"))
      (node (ref "P17") (pin "11") (pinfunction "TMDS_Clock_Shield_11") (pintype "passive"))
    )
    (net (code "155") (name "Net-(P17-TMDS_Data0+)") (class "Default")
      (node (ref "J3") (pin "8") (pinfunction "8_8") (pintype "passive"))
      (node (ref "P17") (pin "7") (pinfunction "TMDS_Data0+_7") (pintype "passive"))
    )
    (net (code "156") (name "Net-(P17-TMDS_Data0-)") (class "Default")
      (node (ref "J3") (pin "9") (pinfunction "9_9") (pintype "passive"))
      (node (ref "P17") (pin "9") (pinfunction "TMDS_Data0-_9") (pintype "passive"))
    )
    (net (code "157") (name "Net-(P17-TMDS_Data0_Shield)") (class "Default")
      (node (ref "J3") (pin "13") (pinfunction "13_13") (pintype "passive"))
      (node (ref "P17") (pin "8") (pinfunction "TMDS_Data0_Shield_8") (pintype "passive"))
    )
    (net (code "158") (name "Net-(P17-TMDS_Data1+)") (class "Default")
      (node (ref "J3") (pin "5") (pinfunction "5_5") (pintype "passive"))
      (node (ref "P17") (pin "4") (pinfunction "TMDS_Data1+_4") (pintype "passive"))
    )
    (net (code "159") (name "Net-(P17-TMDS_Data1-)") (class "Default")
      (node (ref "J3") (pin "6") (pinfunction "6_6") (pintype "passive"))
      (node (ref "P17") (pin "6") (pinfunction "TMDS_Data1-_6") (pintype "passive"))
    )
    (net (code "160") (name "Net-(P17-TMDS_Data1_Shield)") (class "Default")
      (node (ref "J3") (pin "4") (pinfunction "4_4") (pintype "passive"))
      (node (ref "P17") (pin "5") (pinfunction "TMDS_Data1_Shield_5") (pintype "passive"))
    )
    (net (code "161") (name "Net-(P17-TMDS_Data2+)") (class "Default")
      (node (ref "J3") (pin "2") (pinfunction "2_2") (pintype "passive"))
      (node (ref "P17") (pin "1") (pinfunction "TMDS_Data2+_1") (pintype "passive"))
    )
    (net (code "162") (name "Net-(P17-TMDS_Data2_Shield)") (class "Default")
      (node (ref "J3") (pin "7") (pinfunction "7_7") (pintype "passive"))
      (node (ref "P17") (pin "2") (pinfunction "TMDS_Data2_Shield_2") (pintype "passive"))
    )
    (net (code "163") (name "Net-(P17-TMDS_Data2–)") (class "Default")
      (node (ref "J3") (pin "3") (pinfunction "3_3") (pintype "passive"))
      (node (ref "P17") (pin "3") (pinfunction "TMDS_Data2–_3") (pintype "passive"))
    )
    (net (code "164") (name "Net-(P17-Utility_{slash}_HEAC+)") (class "Default")
      (node (ref "J3") (pin "19") (pinfunction "19_19") (pintype "passive"))
      (node (ref "P17") (pin "14") (pinfunction "Utility_/_HEAC+_14") (pintype "passive"))
    )
    (net (code "165") (name "Net-(P18-+5V_Power)") (class "Default")
      (node (ref "J4") (pin "3") (pinfunction "3_3") (pintype "passive"))
      (node (ref "P18") (pin "18") (pinfunction "+5V_Power_18") (pintype "passive"))
    )
    (net (code "166") (name "Net-(P18-CEC)") (class "Default")
      (node (ref "J4") (pin "8") (pinfunction "8_8") (pintype "passive"))
      (node (ref "P18") (pin "13") (pinfunction "CEC_13") (pintype "passive"))
    )
    (net (code "167") (name "Net-(P18-DDC_{slash}_CEC_Ground_{slash}_HEAC_Shield)") (class "Default")
      (node (ref "J4") (pin "4") (pinfunction "4_4") (pintype "passive"))
      (node (ref "P18") (pin "17") (pinfunction "DDC_/_CEC_Ground_/_HEAC_Shield_17") (pintype "passive"))
    )
    (net (code "168") (name "Net-(P18-Hot_Plug_Detect_{slash}_HEAC-)") (class "Default")
      (node (ref "J4") (pin "2") (pinfunction "2_2") (pintype "passive"))
      (node (ref "P18") (pin "19") (pinfunction "Hot_Plug_Detect_/_HEAC-_19") (pintype "passive"))
    )
    (net (code "169") (name "Net-(P18-SCL)") (class "Default")
      (node (ref "J4") (pin "6") (pinfunction "6_6") (pintype "passive"))
      (node (ref "P18") (pin "15") (pinfunction "SCL_15") (pintype "passive"))
    )
    (net (code "170") (name "Net-(P18-SDA)") (class "Default")
      (node (ref "J4") (pin "5") (pinfunction "5_5") (pintype "passive"))
      (node (ref "P18") (pin "16") (pinfunction "SDA_16") (pintype "passive"))
    )
    (net (code "171") (name "Net-(P18-Shield)") (class "Default")
      (node (ref "J4") (pin "1") (pinfunction "1_1") (pintype "passive"))
      (node (ref "P18") (pin "Shell") (pinfunction "Shield_Shell") (pintype "passive"))
    )
    (net (code "172") (name "Net-(P18-TMDS_Clock+)") (class "Default")
      (node (ref "J4") (pin "11") (pinfunction "11_11") (pintype "passive"))
      (node (ref "P18") (pin "10") (pinfunction "TMDS_Clock+_10") (pintype "passive"))
    )
    (net (code "173") (name "Net-(P18-TMDS_Clock-)") (class "Default")
      (node (ref "J4") (pin "9") (pinfunction "9_9") (pintype "passive"))
      (node (ref "P18") (pin "12") (pinfunction "TMDS_Clock-_12") (pintype "passive"))
    )
    (net (code "174") (name "Net-(P18-TMDS_Clock_Shield)") (class "Default")
      (node (ref "J4") (pin "10") (pinfunction "10_10") (pintype "passive"))
      (node (ref "P18") (pin "11") (pinfunction "TMDS_Clock_Shield_11") (pintype "passive"))
    )
    (net (code "175") (name "Net-(P18-TMDS_Data0+)") (class "Default")
      (node (ref "J4") (pin "14") (pinfunction "14_14") (pintype "passive"))
      (node (ref "P18") (pin "7") (pinfunction "TMDS_Data0+_7") (pintype "passive"))
    )
    (net (code "176") (name "Net-(P18-TMDS_Data0-)") (class "Default")
      (node (ref "J4") (pin "12") (pinfunction "12_12") (pintype "passive"))
      (node (ref "P18") (pin "9") (pinfunction "TMDS_Data0-_9") (pintype "passive"))
    )
    (net (code "177") (name "Net-(P18-TMDS_Data0_Shield)") (class "Default")
      (node (ref "J4") (pin "13") (pinfunction "13_13") (pintype "passive"))
      (node (ref "P18") (pin "8") (pinfunction "TMDS_Data0_Shield_8") (pintype "passive"))
    )
    (net (code "178") (name "Net-(P18-TMDS_Data1+)") (class "Default")
      (node (ref "J4") (pin "17") (pinfunction "17_17") (pintype "passive"))
      (node (ref "P18") (pin "4") (pinfunction "TMDS_Data1+_4") (pintype "passive"))
    )
    (net (code "179") (name "Net-(P18-TMDS_Data1-)") (class "Default")
      (node (ref "J4") (pin "15") (pinfunction "15_15") (pintype "passive"))
      (node (ref "P18") (pin "6") (pinfunction "TMDS_Data1-_6") (pintype "passive"))
    )
    (net (code "180") (name "Net-(P18-TMDS_Data1_Shield)") (class "Default")
      (node (ref "J4") (pin "16") (pinfunction "16_16") (pintype "passive"))
      (node (ref "P18") (pin "5") (pinfunction "TMDS_Data1_Shield_5") (pintype "passive"))
    )
    (net (code "181") (name "Net-(P18-TMDS_Data2+)") (class "Default")
      (node (ref "J4") (pin "20") (pinfunction "20_20") (pintype "passive"))
      (node (ref "P18") (pin "1") (pinfunction "TMDS_Data2+_1") (pintype "passive"))
    )
    (net (code "182") (name "Net-(P18-TMDS_Data2_Shield)") (class "Default")
      (node (ref "J4") (pin "19") (pinfunction "19_19") (pintype "passive"))
      (node (ref "P18") (pin "2") (pinfunction "TMDS_Data2_Shield_2") (pintype "passive"))
    )
    (net (code "183") (name "Net-(P18-TMDS_Data2–)") (class "Default")
      (node (ref "J4") (pin "18") (pinfunction "18_18") (pintype "passive"))
      (node (ref "P18") (pin "3") (pinfunction "TMDS_Data2–_3") (pintype "passive"))
    )
    (net (code "184") (name "Net-(P18-Utility_{slash}_HEAC+)") (class "Default")
      (node (ref "J4") (pin "7") (pinfunction "7_7") (pintype "passive"))
      (node (ref "P18") (pin "14") (pinfunction "Utility_/_HEAC+_14") (pintype "passive"))
    )
    (net (code "185") (name "Net-(P19-Pad1)") (class "Default")
      (node (ref "P19") (pin "1") (pinfunction "1_1") (pintype "passive"))
      (node (ref "P20") (pin "A4") (pinfunction "VBUS_A4") (pintype "passive"))
      (node (ref "P20") (pin "A9") (pinfunction "VBUS_A9") (pintype "passive"))
      (node (ref "P20") (pin "B4") (pinfunction "VBUS_B4") (pintype "passive"))
      (node (ref "P20") (pin "B9") (pinfunction "VBUS_B9") (pintype "passive"))
    )
    (net (code "186") (name "Net-(P19-Pad2)") (class "Default")
      (node (ref "P19") (pin "2") (pinfunction "2_2") (pintype "passive"))
      (node (ref "P20") (pin "A7") (pinfunction "D-_A7") (pintype "passive"))
      (node (ref "P20") (pin "B7") (pinfunction "D-_B7") (pintype "passive"))
    )
    (net (code "187") (name "Net-(P19-Pad3)") (class "Default")
      (node (ref "P19") (pin "3") (pinfunction "3_3") (pintype "passive"))
      (node (ref "P20") (pin "A6") (pinfunction "D+_A6") (pintype "passive"))
      (node (ref "P20") (pin "B6") (pinfunction "D+_B6") (pintype "passive"))
    )
    (net (code "188") (name "Net-(P19-Pad4)") (class "Default")
      (node (ref "P19") (pin "4") (pinfunction "4_4") (pintype "passive"))
      (node (ref "P20") (pin "A1") (pinfunction "GND_A1") (pintype "passive"))
      (node (ref "P20") (pin "A12") (pinfunction "GND_A12") (pintype "passive"))
      (node (ref "P20") (pin "B1") (pinfunction "GND_B1") (pintype "passive"))
      (node (ref "P20") (pin "B12") (pinfunction "GND_B12") (pintype "passive"))
      (node (ref "P20") (pin "Shield") (pinfunction "Shield_Shield") (pintype "passive"))
      (node (ref "R1") (pin "1") (pinfunction "1_1") (pintype "passive"))
      (node (ref "R2") (pin "1") (pinfunction "1_1") (pintype "passive"))
    )
    (net (code "189") (name "Net-(P20-CC1)") (class "Default")
      (node (ref "P20") (pin "A5") (pinfunction "CC1_A5") (pintype "passive"))
      (node (ref "R1") (pin "2") (pinfunction "2_2") (pintype "passive"))
    )
    (net (code "190") (name "Net-(P20-CC2)") (class "Default")
      (node (ref "P20") (pin "B5") (pinfunction "CC2_B5") (pintype "passive"))
      (node (ref "R2") (pin "2") (pinfunction "2_2") (pintype "passive"))
    )
    (net (code "191") (name "unconnected-(J1-PadMP1)") (class "Default")
      (node (ref "J1") (pin "MP1") (pinfunction "MP1_MP1") (pintype "passive"))
    )
    (net (code "192") (name "unconnected-(J1-PadMP2)") (class "Default")
      (node (ref "J1") (pin "MP2") (pinfunction "MP2_MP2") (pintype "passive"))
    )
    (net (code "193") (name "unconnected-(J2-PadMP1)") (class "Default")
      (node (ref "J2") (pin "MP1") (pinfunction "MP1_MP1") (pintype "passive"))
    )
    (net (code "194") (name "unconnected-(J2-PadMP2)") (class "Default")
      (node (ref "J2") (pin "MP2") (pinfunction "MP2_MP2") (pintype "passive"))
    )
    (net (code "195") (name "unconnected-(J3-PadMP1)") (class "Default")
      (node (ref "J3") (pin "MP1") (pinfunction "MP1_MP1") (pintype "passive"))
    )
    (net (code "196") (name "unconnected-(J3-PadMP2)") (class "Default")
      (node (ref "J3") (pin "MP2") (pinfunction "MP2_MP2") (pintype "passive"))
    )
    (net (code "197") (name "unconnected-(J4-PadMP1)") (class "Default")
      (node (ref "J4") (pin "MP1") (pinfunction "MP1_MP1") (pintype "passive"))
    )
    (net (code "198") (name "unconnected-(J4-PadMP2)") (class "Default")
      (node (ref "J4") (pin "MP2") (pinfunction "MP2_MP2") (pintype "passive"))
    )
    (net (code "199") (name "unconnected-(P1-SHLD1-Pad5)") (class "Default")
      (node (ref "P1") (pin "5") (pinfunction "SHLD1_5") (pintype "passive"))
    )
    (net (code "200") (name "unconnected-(P1-SHLD2-Pad6)") (class "Default")
      (node (ref "P1") (pin "6") (pinfunction "SHLD2_6") (pintype "passive"))
    )
    (net (code "201") (name "unconnected-(P12-PadMP1)") (class "Default")
      (node (ref "P12") (pin "MP1") (pinfunction "MP1_MP1") (pintype "passive"))
    )
    (net (code "202") (name "unconnected-(P12-PadMP2)") (class "Default")
      (node (ref "P12") (pin "MP2") (pinfunction "MP2_MP2") (pintype "passive"))
    )
  )
)
